# LEDs_FMU3_REV_G.net
KiCad netlist of a schematic drawn in Altium Designer
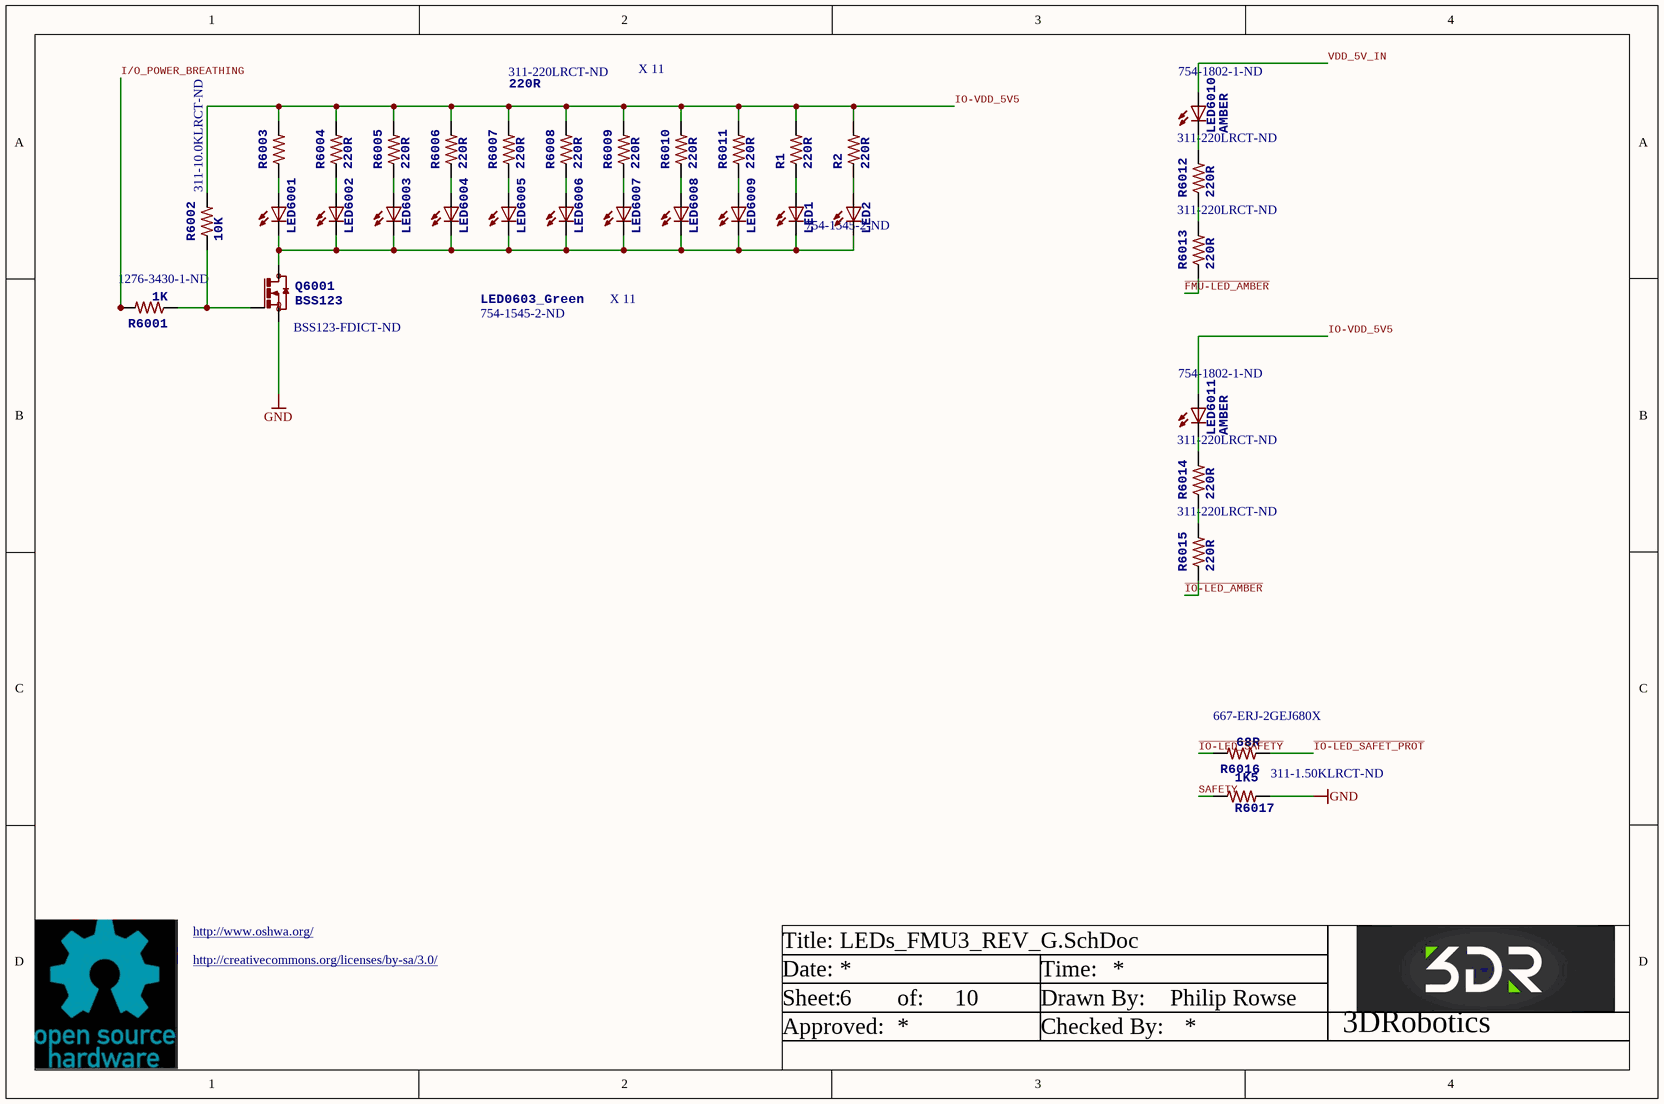
[diagram p0: LEDs_FMU3_REV_G.SchDoc]

(export (version "E")
  (design (tool "Eeschema 10.0.6"))
  (components
    (comp (ref "LED1")
      (value "LED0603_Green")
      (footprint "0603-LED-Blue")
      (description "LED GREEN ROUND CLEAR SMD")
      (fields
        (field (name "SUPPLIER PART NUMBER 1") "754-1545-2-ND")
        (field (name "3DR_PARTNO") "ECM0494")
        (field (name "PARTNO") "APTD1608CGCK")
      )
      (libsource (lib "pixhawk2") (part "LED0603_Blue"))
    )
    (comp (ref "LED2")
      (value "LED0603_Green")
      (footprint "0603-LED-Blue")
      (description "LED GREEN ROUND CLEAR SMD")
      (fields (field (name "3DR_PARTNO") "ECM0494") (field (name "PARTNO") "APTD1608CGCK"))
      (libsource (lib "pixhawk2") (part "LED0603_Blue"))
    )
    (comp (ref "LED6001")
      (value "LED0603_Green")
      (footprint "0603-LED-Blue")
      (description "LED GREEN ROUND CLEAR SMD")
      (fields
        (field (name "SUPPLIER PART NUMBER 1") "754-1545-2-ND")
        (field (name "3DR_PARTNO") "ECM0494")
        (field (name "PARTNO") "APTD1608CGCK")
      )
      (libsource (lib "pixhawk2") (part "LED0603_Blue"))
    )
    (comp (ref "LED6002")
      (value "LED0603_Green")
      (footprint "0603-LED-Blue")
      (description "LED GREEN ROUND CLEAR SMD")
      (fields (field (name "3DR_PARTNO") "ECM0494") (field (name "PARTNO") "APTD1608CGCK"))
      (libsource (lib "pixhawk2") (part "LED0603_Blue"))
    )
    (comp (ref "LED6003")
      (value "LED0603_Green")
      (footprint "0603-LED-Blue")
      (description "LED GREEN ROUND CLEAR SMD")
      (fields (field (name "3DR_PARTNO") "ECM0494") (field (name "PARTNO") "APTD1608CGCK"))
      (libsource (lib "pixhawk2") (part "LED0603_Blue"))
    )
    (comp (ref "LED6004")
      (value "LED0603_Green")
      (footprint "0603-LED-Blue")
      (description "LED GREEN ROUND CLEAR SMD")
      (fields (field (name "3DR_PARTNO") "ECM0494") (field (name "PARTNO") "APTD1608CGCK"))
      (libsource (lib "pixhawk2") (part "LED0603_Blue"))
    )
    (comp (ref "LED6005")
      (value "LED0603_Green")
      (footprint "0603-LED-Blue")
      (description "LED GREEN ROUND CLEAR SMD")
      (fields (field (name "3DR_PARTNO") "ECM0494") (field (name "PARTNO") "APTD1608CGCK"))
      (libsource (lib "pixhawk2") (part "LED0603_Blue"))
    )
    (comp (ref "LED6006")
      (value "LED0603_Green")
      (footprint "0603-LED-Blue")
      (description "LED GREEN ROUND CLEAR SMD")
      (fields (field (name "3DR_PARTNO") "ECM0494") (field (name "PARTNO") "APTD1608CGCK"))
      (libsource (lib "pixhawk2") (part "LED0603_Blue"))
    )
    (comp (ref "LED6007")
      (value "LED0603_Green")
      (footprint "0603-LED-Blue")
      (description "LED GREEN ROUND CLEAR SMD")
      (fields (field (name "3DR_PARTNO") "ECM0494") (field (name "PARTNO") "APTD1608CGCK"))
      (libsource (lib "pixhawk2") (part "LED0603_Blue"))
    )
    (comp (ref "LED6008")
      (value "LED0603_Green")
      (footprint "0603-LED-Blue")
      (description "LED GREEN ROUND CLEAR SMD")
      (fields (field (name "3DR_PARTNO") "ECM0494") (field (name "PARTNO") "APTD1608CGCK"))
      (libsource (lib "pixhawk2") (part "LED0603_Blue"))
    )
    (comp (ref "LED6009")
      (value "LED0603_Green")
      (footprint "0603-LED-Blue")
      (description "LED GREEN ROUND CLEAR SMD")
      (fields (field (name "3DR_PARTNO") "ECM0494") (field (name "PARTNO") "APTD1608CGCK"))
      (libsource (lib "pixhawk2") (part "LED0603_Blue"))
    )
    (comp (ref "LED6010")
      (value "AMBER")
      (footprint "0603-LED")
      (description "LED 1.6X0.8 DOME ORN CLEAR SMD")
      (fields
        (field (name "PARTNO") "APTD1608SECK")
        (field (name "SUPPLIER PART NUMBER 1") "754-1802-1-ND")
        (field (name "3DR_PARTNO") "ECM0515")
      )
      (libsource (lib "pixhawk2") (part "LED0603"))
    )
    (comp (ref "LED6011")
      (value "AMBER")
      (footprint "0603-LED")
      (description "LED 1.6X0.8 DOME ORN CLEAR SMD")
      (fields
        (field (name "PARTNO") "APTD1608SECK")
        (field (name "SUPPLIER PART NUMBER 1") "754-1802-1-ND")
        (field (name "3DR_PARTNO") "ECM0515")
      )
      (libsource (lib "pixhawk2") (part "LED0603"))
    )
    (comp (ref "Q6001")
      (value "BSS123")
      (footprint "SOT23")
      (description "MOSFET N-CH 100V 170MA SOT23-3")
      (fields (field (name "SUPPLIER PART NUMBER 1") "BSS123-FDICT-ND") (field (name "3DR_PARTNO") "ECM0547"))
      (libsource (lib "transistor-small-signal") (part "BSS123"))
    )
    (comp (ref "R1")
      (value "220R")
      (footprint "0402-RES")
      (description "RES 220 OHM 1/16W 1% 0402 SMD")
      (fields (field (name "PARTNO") "RC0402FR-07220RL") (field (name "3DR_PARTNO") "ECM0821"))
      (libsource (lib "pixhawk2") (part "RESISTOR0402-RES"))
    )
    (comp (ref "R2")
      (value "220R")
      (footprint "0402-RES")
      (description "RES 220 OHM 1/16W 1% 0402 SMD")
      (fields (field (name "PARTNO") "RC0402FR-07220RL") (field (name "3DR_PARTNO") "ECM0821"))
      (libsource (lib "pixhawk2") (part "RESISTOR0402-RES"))
    )
    (comp (ref "R6001")
      (value "1K")
      (footprint "0402-RES")
      (description "RES 1K OHM 1/16W 1% 0402")
      (fields
        (field (name "PARTNO") "RC1005F102CS")
        (field (name "SUPPLIER PART NUMBER 1") "1276-3430-1-ND")
        (field (name "3DR_PARTNO") "ECM0804")
      )
      (libsource (lib "pixhawk2") (part "RESISTOR0402-RES"))
    )
    (comp (ref "R6002")
      (value "10K")
      (footprint "0402-RES")
      (description "RES 10K OHM 1/16W 1% 0402 SMD")
      (fields
        (field (name "PARTNO") "RC0402FR-0710KL")
        (field (name "SUPPLIER PART NUMBER 1") "311-10.0KLRCT-ND")
        (field (name "3DR_PARTNO") "ECM0800")
      )
      (libsource (lib "pixhawk2") (part "RESISTOR0402-RES"))
    )
    (comp (ref "R6003")
      (value "220R")
      (footprint "0402-RES")
      (description "RES 220 OHM 1/16W 1% 0402 SMD")
      (fields
        (field (name "PARTNO") "RC0402FR-07220RL")
        (field (name "SUPPLIER PART NUMBER 1") "311-220LRCT-ND")
        (field (name "3DR_PARTNO") "ECM0821")
      )
      (libsource (lib "pixhawk2") (part "RESISTOR0402-RES"))
    )
    (comp (ref "R6004")
      (value "220R")
      (footprint "0402-RES")
      (description "RES 220 OHM 1/16W 1% 0402 SMD")
      (fields (field (name "PARTNO") "RC0402FR-07220RL") (field (name "3DR_PARTNO") "ECM0821"))
      (libsource (lib "pixhawk2") (part "RESISTOR0402-RES"))
    )
    (comp (ref "R6005")
      (value "220R")
      (footprint "0402-RES")
      (description "RES 220 OHM 1/16W 1% 0402 SMD")
      (fields (field (name "PARTNO") "RC0402FR-07220RL") (field (name "3DR_PARTNO") "ECM0821"))
      (libsource (lib "pixhawk2") (part "RESISTOR0402-RES"))
    )
    (comp (ref "R6006")
      (value "220R")
      (footprint "0402-RES")
      (description "RES 220 OHM 1/16W 1% 0402 SMD")
      (fields (field (name "PARTNO") "RC0402FR-07220RL") (field (name "3DR_PARTNO") "ECM0821"))
      (libsource (lib "pixhawk2") (part "RESISTOR0402-RES"))
    )
    (comp (ref "R6007")
      (value "220R")
      (footprint "0402-RES")
      (description "RES 220 OHM 1/16W 1% 0402 SMD")
      (fields (field (name "PARTNO") "RC0402FR-07220RL") (field (name "3DR_PARTNO") "ECM0821"))
      (libsource (lib "pixhawk2") (part "RESISTOR0402-RES"))
    )
    (comp (ref "R6008")
      (value "220R")
      (footprint "0402-RES")
      (description "RES 220 OHM 1/16W 1% 0402 SMD")
      (fields (field (name "PARTNO") "RC0402FR-07220RL") (field (name "3DR_PARTNO") "ECM0821"))
      (libsource (lib "pixhawk2") (part "RESISTOR0402-RES"))
    )
    (comp (ref "R6009")
      (value "220R")
      (footprint "0402-RES")
      (description "RES 220 OHM 1/16W 1% 0402 SMD")
      (fields (field (name "PARTNO") "RC0402FR-07220RL") (field (name "3DR_PARTNO") "ECM0821"))
      (libsource (lib "pixhawk2") (part "RESISTOR0402-RES"))
    )
    (comp (ref "R6010")
      (value "220R")
      (footprint "0402-RES")
      (description "RES 220 OHM 1/16W 1% 0402 SMD")
      (fields (field (name "PARTNO") "RC0402FR-07220RL") (field (name "3DR_PARTNO") "ECM0821"))
      (libsource (lib "pixhawk2") (part "RESISTOR0402-RES"))
    )
    (comp (ref "R6011")
      (value "220R")
      (footprint "0402-RES")
      (description "RES 220 OHM 1/16W 1% 0402 SMD")
      (fields (field (name "PARTNO") "RC0402FR-07220RL") (field (name "3DR_PARTNO") "ECM0821"))
      (libsource (lib "pixhawk2") (part "RESISTOR0402-RES"))
    )
    (comp (ref "R6012")
      (value "220R")
      (footprint "0402-RES")
      (description "RES 220 OHM 1/16W 1% 0402 SMD")
      (fields
        (field (name "PARTNO") "RC0402FR-07220RL")
        (field (name "SUPPLIER PART NUMBER 1") "311-220LRCT-ND")
        (field (name "3DR_PARTNO") "ECM0821")
      )
      (libsource (lib "pixhawk2") (part "RESISTOR0402-RES"))
    )
    (comp (ref "R6013")
      (value "220R")
      (footprint "0402-RES")
      (description "RES 220 OHM 1/16W 1% 0402 SMD")
      (fields
        (field (name "PARTNO") "RC0402FR-07220RL")
        (field (name "SUPPLIER PART NUMBER 1") "311-220LRCT-ND")
        (field (name "3DR_PARTNO") "ECM0821")
      )
      (libsource (lib "pixhawk2") (part "RESISTOR0402-RES"))
    )
    (comp (ref "R6014")
      (value "220R")
      (footprint "0402-RES")
      (description "RES 220 OHM 1/16W 1% 0402 SMD")
      (fields
        (field (name "PARTNO") "RC0402FR-07220RL")
        (field (name "SUPPLIER PART NUMBER 1") "311-220LRCT-ND")
        (field (name "3DR_PARTNO") "ECM0821")
      )
      (libsource (lib "pixhawk2") (part "RESISTOR0402-RES"))
    )
    (comp (ref "R6015")
      (value "220R")
      (footprint "0402-RES")
      (description "RES 220 OHM 1/16W 1% 0402 SMD")
      (fields
        (field (name "PARTNO") "RC0402FR-07220RL")
        (field (name "SUPPLIER PART NUMBER 1") "311-220LRCT-ND")
        (field (name "3DR_PARTNO") "ECM0821")
      )
      (libsource (lib "pixhawk2") (part "RESISTOR0402-RES"))
    )
    (comp (ref "R6016")
      (value "68R")
      (footprint "0402-RES")
      (description "Thick Film Resistors - SMD 0402 68ohms 5% Tol")
      (fields
        (field (name "PARTNO") "ERJ-2GEJ680X")
        (field (name "SUPPLIER PART NUMBER 1") "667-ERJ-2GEJ680X")
        (field (name "3DR_PARTNO") "ECM0816")
      )
      (libsource (lib "pixhawk2") (part "RESISTOR0402-RES"))
    )
    (comp (ref "R6017")
      (value "1K5")
      (footprint "0402-RES")
      (description "RES 1.5K OHM 1/16W 1% 0402 SMD")
      (fields
        (field (name "SUPPLIER PART NUMBER 1") "311-1.50KLRCT-ND")
        (field (name "3DR_PARTNO") "ECM0803")
        (field (name "PARTNO") "RC0402FR-071K5L")
      )
      (libsource (lib "pixhawk2") (part "RESISTOR0402-RES"))
    )
  )
  (nets
    (net (code "1") (name "/IO-VDD_5V5") (class "Default")
      (node (ref "LED6011") (pin "A") (pinfunction "A_A") (pintype "passive"))
      (node (ref "R1") (pin "P$2") (pinfunction "2_P$2") (pintype "passive"))
      (node (ref "R2") (pin "P$2") (pinfunction "2_P$2") (pintype "passive"))
      (node (ref "R6002") (pin "P$2") (pinfunction "2_P$2") (pintype "passive"))
      (node (ref "R6003") (pin "P$2") (pinfunction "2_P$2") (pintype "passive"))
      (node (ref "R6004") (pin "P$2") (pinfunction "2_P$2") (pintype "passive"))
      (node (ref "R6005") (pin "P$2") (pinfunction "2_P$2") (pintype "passive"))
      (node (ref "R6006") (pin "P$2") (pinfunction "2_P$2") (pintype "passive"))
      (node (ref "R6007") (pin "P$2") (pinfunction "2_P$2") (pintype "passive"))
      (node (ref "R6008") (pin "P$2") (pinfunction "2_P$2") (pintype "passive"))
      (node (ref "R6009") (pin "P$2") (pinfunction "2_P$2") (pintype "passive"))
      (node (ref "R6010") (pin "P$2") (pinfunction "2_P$2") (pintype "passive"))
      (node (ref "R6011") (pin "P$2") (pinfunction "2_P$2") (pintype "passive"))
    )
    (net (code "2") (name "/I{slash}O_POWER_BREATHING") (class "Default")
      (node (ref "R6001") (pin "P$2") (pinfunction "2_P$2") (pintype "passive"))
    )
    (net (code "3") (name "/SAFETY") (class "Default")
      (node (ref "R6017") (pin "P$1") (pinfunction "1_P$1") (pintype "passive"))
    )
    (net (code "4") (name "/VDD_5V_IN") (class "Default")
      (node (ref "LED6010") (pin "A") (pinfunction "A_A") (pintype "passive"))
    )
    (net (code "5") (name "/~{FMU-LED_AMBER}") (class "Default")
      (node (ref "R6013") (pin "P$1") (pinfunction "1_P$1") (pintype "passive"))
    )
    (net (code "6") (name "/~{IO-LED_AMBER}") (class "Default")
      (node (ref "R6015") (pin "P$1") (pinfunction "1_P$1") (pintype "passive"))
    )
    (net (code "7") (name "/~{IO-LED_SAFETY}") (class "Default")
      (node (ref "R6016") (pin "P$2") (pinfunction "2_P$2") (pintype "passive"))
    )
    (net (code "8") (name "/~{IO-LED_SAFET_PROT}") (class "Default")
      (node (ref "R6016") (pin "P$1") (pinfunction "1_P$1") (pintype "passive"))
    )
    (net (code "9") (name "GND") (class "Default")
      (node (ref "Q6001") (pin "2") (pinfunction "S_2") (pintype "passive"))
      (node (ref "R6017") (pin "P$2") (pinfunction "2_P$2") (pintype "passive"))
    )
    (net (code "10") (name "Net-(Q6001-D)") (class "Default")
      (node (ref "LED1") (pin "C") (pinfunction "C_C") (pintype "passive"))
      (node (ref "LED2") (pin "C") (pinfunction "C_C") (pintype "passive"))
      (node (ref "LED6001") (pin "C") (pinfunction "C_C") (pintype "passive"))
      (node (ref "LED6002") (pin "C") (pinfunction "C_C") (pintype "passive"))
      (node (ref "LED6003") (pin "C") (pinfunction "C_C") (pintype "passive"))
      (node (ref "LED6004") (pin "C") (pinfunction "C_C") (pintype "passive"))
      (node (ref "LED6005") (pin "C") (pinfunction "C_C") (pintype "passive"))
      (node (ref "LED6006") (pin "C") (pinfunction "C_C") (pintype "passive"))
      (node (ref "LED6007") (pin "C") (pinfunction "C_C") (pintype "passive"))
      (node (ref "LED6008") (pin "C") (pinfunction "C_C") (pintype "passive"))
      (node (ref "LED6009") (pin "C") (pinfunction "C_C") (pintype "passive"))
      (node (ref "Q6001") (pin "3") (pinfunction "D_3") (pintype "passive"))
    )
    (net (code "11") (name "Net-(Q6001-G)") (class "Default")
      (node (ref "Q6001") (pin "1") (pinfunction "G_1") (pintype "passive"))
      (node (ref "R6001") (pin "P$1") (pinfunction "1_P$1") (pintype "passive"))
      (node (ref "R6002") (pin "P$1") (pinfunction "1_P$1") (pintype "passive"))
    )
    (net (code "12") (name "Net-(R1-1)") (class "Default")
      (node (ref "LED1") (pin "A") (pinfunction "A_A") (pintype "passive"))
      (node (ref "R1") (pin "P$1") (pinfunction "1_P$1") (pintype "passive"))
    )
    (net (code "13") (name "Net-(R2-1)") (class "Default")
      (node (ref "LED2") (pin "A") (pinfunction "A_A") (pintype "passive"))
      (node (ref "R2") (pin "P$1") (pinfunction "1_P$1") (pintype "passive"))
    )
    (net (code "14") (name "Net-(R6003-1)") (class "Default")
      (node (ref "LED6001") (pin "A") (pinfunction "A_A") (pintype "passive"))
      (node (ref "R6003") (pin "P$1") (pinfunction "1_P$1") (pintype "passive"))
    )
    (net (code "15") (name "Net-(R6004-1)") (class "Default")
      (node (ref "LED6002") (pin "A") (pinfunction "A_A") (pintype "passive"))
      (node (ref "R6004") (pin "P$1") (pinfunction "1_P$1") (pintype "passive"))
    )
    (net (code "16") (name "Net-(R6005-1)") (class "Default")
      (node (ref "LED6003") (pin "A") (pinfunction "A_A") (pintype "passive"))
      (node (ref "R6005") (pin "P$1") (pinfunction "1_P$1") (pintype "passive"))
    )
    (net (code "17") (name "Net-(R6006-1)") (class "Default")
      (node (ref "LED6004") (pin "A") (pinfunction "A_A") (pintype "passive"))
      (node (ref "R6006") (pin "P$1") (pinfunction "1_P$1") (pintype "passive"))
    )
    (net (code "18") (name "Net-(R6007-1)") (class "Default")
      (node (ref "LED6005") (pin "A") (pinfunction "A_A") (pintype "passive"))
      (node (ref "R6007") (pin "P$1") (pinfunction "1_P$1") (pintype "passive"))
    )
    (net (code "19") (name "Net-(R6008-1)") (class "Default")
      (node (ref "LED6006") (pin "A") (pinfunction "A_A") (pintype "passive"))
      (node (ref "R6008") (pin "P$1") (pinfunction "1_P$1") (pintype "passive"))
    )
    (net (code "20") (name "Net-(R6009-1)") (class "Default")
      (node (ref "LED6007") (pin "A") (pinfunction "A_A") (pintype "passive"))
      (node (ref "R6009") (pin "P$1") (pinfunction "1_P$1") (pintype "passive"))
    )
    (net (code "21") (name "Net-(R6010-1)") (class "Default")
      (node (ref "LED6008") (pin "A") (pinfunction "A_A") (pintype "passive"))
      (node (ref "R6010") (pin "P$1") (pinfunction "1_P$1") (pintype "passive"))
    )
    (net (code "22") (name "Net-(R6011-1)") (class "Default")
      (node (ref "LED6009") (pin "A") (pinfunction "A_A") (pintype "passive"))
      (node (ref "R6011") (pin "P$1") (pinfunction "1_P$1") (pintype "passive"))
    )
    (net (code "23") (name "Net-(R6012-1)") (class "Default")
      (node (ref "R6012") (pin "P$1") (pinfunction "1_P$1") (pintype "passive"))
      (node (ref "R6013") (pin "P$2") (pinfunction "2_P$2") (pintype "passive"))
    )
    (net (code "24") (name "Net-(R6012-2)") (class "Default")
      (node (ref "LED6010") (pin "C") (pinfunction "C_C") (pintype "passive"))
      (node (ref "R6012") (pin "P$2") (pinfunction "2_P$2") (pintype "passive"))
    )
    (net (code "25") (name "Net-(R6014-1)") (class "Default")
      (node (ref "R6014") (pin "P$1") (pinfunction "1_P$1") (pintype "passive"))
      (node (ref "R6015") (pin "P$2") (pinfunction "2_P$2") (pintype "passive"))
    )
    (net (code "26") (name "Net-(R6014-2)") (class "Default")
      (node (ref "LED6011") (pin "C") (pinfunction "C_C") (pintype "passive"))
      (node (ref "R6014") (pin "P$2") (pinfunction "2_P$2") (pintype "passive"))
    )
  )
)
